# 03_-_Convert.net
KiCad netlist of a schematic drawn in Altium Designer
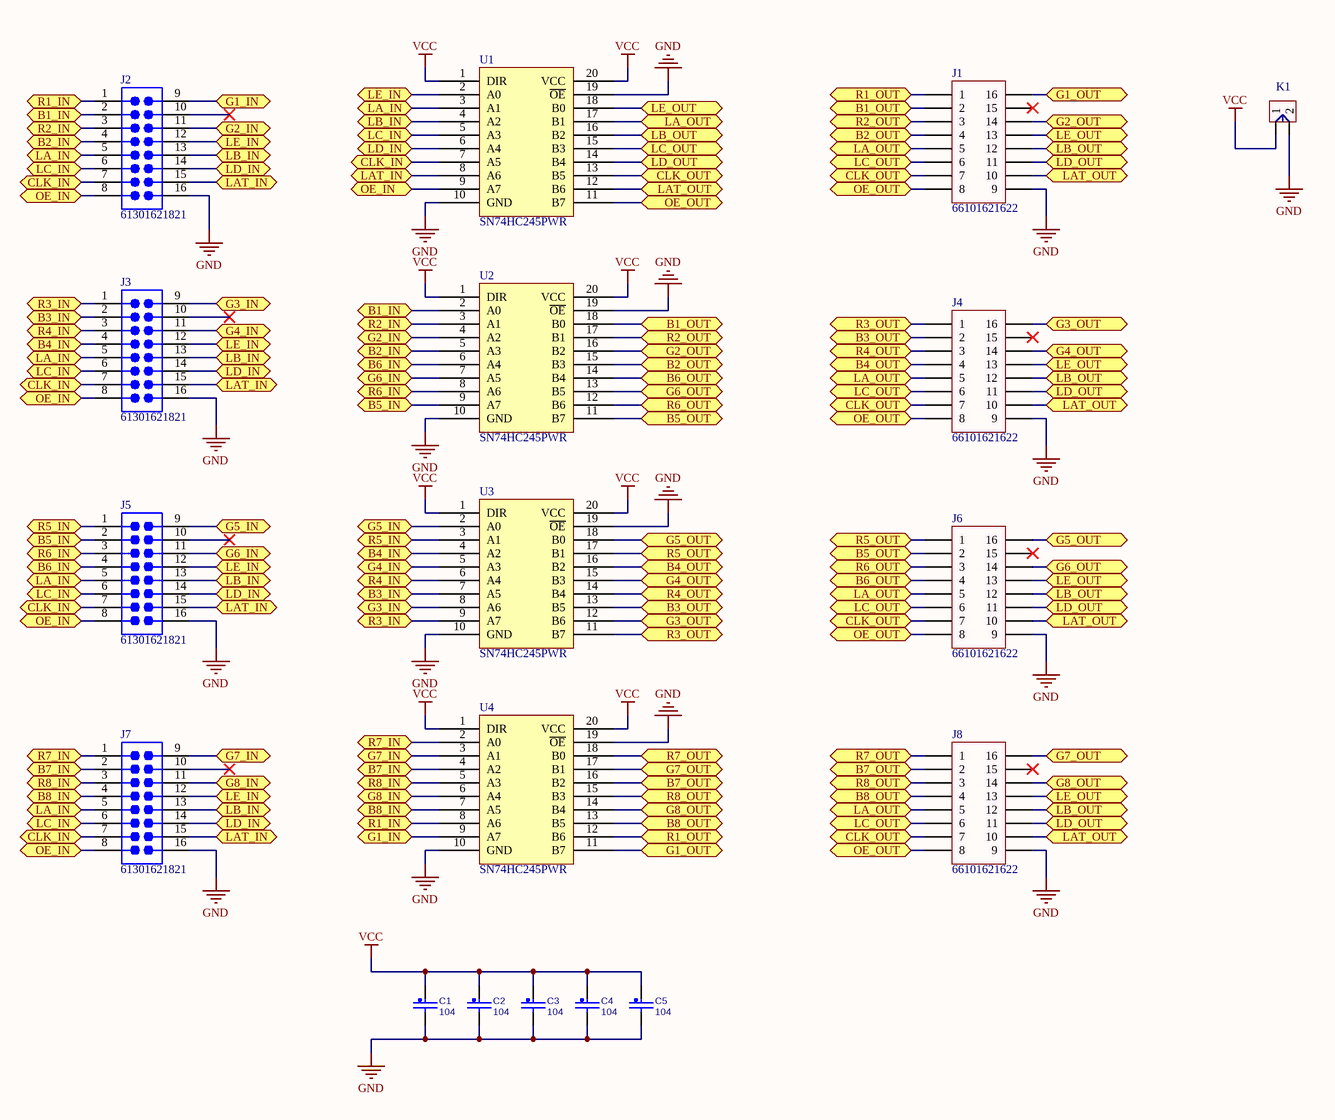
[diagram p0: [03] - Convert.SchDoc]

(export (version "E")
  (design (tool "Eeschema 10.0.6"))
  (components
    (comp (ref "C1")
      (value "104")
      (footprint "C0805")
      (description "Surface Mound Multilayer Ceramic Chip Capacitor (SMD MLCC)")
      (fields
        (field (name "MANUFACTURER") "TDK Corporation")
        (field (name "MANUFACTURER PART NUMBER") "C2012X5R1C226K")
        (field (name ".CHECKED PCB") "RF")
        (field (name ".CHECKED SCH") "RF")
      )
      (libsource (lib "StdLib") (part "CAP-SMD-CERAMIC"))
    )
    (comp (ref "C2")
      (value "104")
      (footprint "C0805")
      (description "Surface Mound Multilayer Ceramic Chip Capacitor (SMD MLCC)")
      (fields
        (field (name "MANUFACTURER") "TDK Corporation")
        (field (name "MANUFACTURER PART NUMBER") "C2012X5R1C226K")
        (field (name ".CHECKED PCB") "RF")
        (field (name ".CHECKED SCH") "RF")
      )
      (libsource (lib "StdLib") (part "CAP-SMD-CERAMIC"))
    )
    (comp (ref "C3")
      (value "104")
      (footprint "C0805")
      (description "Surface Mound Multilayer Ceramic Chip Capacitor (SMD MLCC)")
      (fields
        (field (name "MANUFACTURER") "TDK Corporation")
        (field (name "MANUFACTURER PART NUMBER") "C2012X5R1C226K")
        (field (name ".CHECKED PCB") "RF")
        (field (name ".CHECKED SCH") "RF")
      )
      (libsource (lib "StdLib") (part "CAP-SMD-CERAMIC"))
    )
    (comp (ref "C4")
      (value "104")
      (footprint "C0805")
      (description "Surface Mound Multilayer Ceramic Chip Capacitor (SMD MLCC)")
      (fields
        (field (name "MANUFACTURER") "TDK Corporation")
        (field (name "MANUFACTURER PART NUMBER") "C2012X5R1C226K")
        (field (name ".CHECKED PCB") "RF")
        (field (name ".CHECKED SCH") "RF")
      )
      (libsource (lib "StdLib") (part "CAP-SMD-CERAMIC"))
    )
    (comp (ref "C5")
      (value "104")
      (footprint "C0805")
      (description "Surface Mound Multilayer Ceramic Chip Capacitor (SMD MLCC)")
      (fields
        (field (name "MANUFACTURER") "TDK Corporation")
        (field (name "MANUFACTURER PART NUMBER") "C2012X5R1C226K")
        (field (name ".CHECKED PCB") "RF")
        (field (name ".CHECKED SCH") "RF")
      )
      (libsource (lib "StdLib") (part "CAP-SMD-CERAMIC"))
    )
    (comp (ref "J1")
      (value "66101621622")
      (footprint "66101621622")
      (fields (field (name "MANUFACTURER") "Wurth Elektronik") (field (name "CREATED BY") "Baojun Chen"))
      (libsource (lib "Library") (part "LHeader 16 Dual 2.54MM"))
    )
    (comp (ref "J2")
      (value "61301621821")
      (footprint "61301621821")
      (description "2.54 mm Dual Socket Header, 16p")
      (fields (field (name "PUBLISHER") "Wurth Elektronik"))
      (libsource (lib "Library") (part "JP8 2.54MM Dual Socket"))
    )
    (comp (ref "J3")
      (value "61301621821")
      (footprint "61301621821")
      (description "2.54 mm Dual Socket Header, 16p")
      (fields (field (name "PUBLISHER") "Wurth Elektronik"))
      (libsource (lib "Library") (part "JP8 2.54MM Dual Socket"))
    )
    (comp (ref "J4")
      (value "66101621622")
      (footprint "66101621622")
      (fields (field (name "MANUFACTURER") "Wurth Elektronik") (field (name "CREATED BY") "Baojun Chen"))
      (libsource (lib "Library") (part "LHeader 16 Dual 2.54MM"))
    )
    (comp (ref "J5")
      (value "61301621821")
      (footprint "61301621821")
      (description "2.54 mm Dual Socket Header, 16p")
      (fields (field (name "PUBLISHER") "Wurth Elektronik"))
      (libsource (lib "Library") (part "JP8 2.54MM Dual Socket"))
    )
    (comp (ref "J6")
      (value "66101621622")
      (footprint "66101621622")
      (fields (field (name "MANUFACTURER") "Wurth Elektronik") (field (name "CREATED BY") "Baojun Chen"))
      (libsource (lib "Library") (part "LHeader 16 Dual 2.54MM"))
    )
    (comp (ref "J7")
      (value "61301621821")
      (footprint "61301621821")
      (description "2.54 mm Dual Socket Header, 16p")
      (fields (field (name "PUBLISHER") "Wurth Elektronik"))
      (libsource (lib "Library") (part "JP8 2.54MM Dual Socket"))
    )
    (comp (ref "J8")
      (value "66101621622")
      (footprint "66101621622")
      (fields (field (name "MANUFACTURER") "Wurth Elektronik") (field (name "CREATED BY") "Baojun Chen"))
      (libsource (lib "Library") (part "LHeader 16 Dual 2.54MM"))
    )
    (comp (ref "K1")
      (value "KF2")
      (footprint "KF5.08 2DV")
      (description "KF2, 5.08mm, 10A, 300V, -40C ~ 105C")
      (libsource (lib "Library") (part "KF2"))
    )
    (comp (ref "U1")
      (value "SN74HC245PWR")
      (footprint "TSSOP65P440X650-20N")
      (description "IC Bus Transceiver 8 Bit 20TSSOP / Bus Xcvr Single 8-CH 3-ST 20-PIN TSSOP T/r")
      (fields (field (name "MANUFACTURER") "Texas Instruments"))
      (libsource (lib "StdLib") (part "SN74HC245PWR"))
    )
    (comp (ref "U2")
      (value "SN74HC245PWR")
      (footprint "TSSOP65P440X650-20N")
      (description "IC Bus Transceiver 8 Bit 20TSSOP / Bus Xcvr Single 8-CH 3-ST 20-PIN TSSOP T/r")
      (fields (field (name "MANUFACTURER") "Texas Instruments"))
      (libsource (lib "StdLib") (part "SN74HC245PWR"))
    )
    (comp (ref "U3")
      (value "SN74HC245PWR")
      (footprint "TSSOP65P440X650-20N")
      (description "IC Bus Transceiver 8 Bit 20TSSOP / Bus Xcvr Single 8-CH 3-ST 20-PIN TSSOP T/r")
      (fields (field (name "MANUFACTURER") "Texas Instruments"))
      (libsource (lib "StdLib") (part "SN74HC245PWR"))
    )
    (comp (ref "U4")
      (value "SN74HC245PWR")
      (footprint "TSSOP65P440X650-20N")
      (description "IC Bus Transceiver 8 Bit 20TSSOP / Bus Xcvr Single 8-CH 3-ST 20-PIN TSSOP T/r")
      (fields (field (name "MANUFACTURER") "Texas Instruments"))
      (libsource (lib "StdLib") (part "SN74HC245PWR"))
    )
  )
  (nets
    (net (code "1") (name "/B1_IN") (class "Default")
      (node (ref "J2") (pin "2") (pinfunction "2_2") (pintype "passive"))
      (node (ref "U2") (pin "2") (pinfunction "A0_2") (pintype "passive"))
    )
    (net (code "2") (name "/B1_OUT") (class "Default")
      (node (ref "J1") (pin "2") (pinfunction "2_2") (pintype "passive"))
      (node (ref "U2") (pin "18") (pinfunction "B0_18") (pintype "passive"))
    )
    (net (code "3") (name "/B2_IN") (class "Default")
      (node (ref "J2") (pin "4") (pinfunction "4_4") (pintype "passive"))
      (node (ref "U2") (pin "5") (pinfunction "A3_5") (pintype "passive"))
    )
    (net (code "4") (name "/B2_OUT") (class "Default")
      (node (ref "J1") (pin "4") (pinfunction "4_4") (pintype "passive"))
      (node (ref "U2") (pin "15") (pinfunction "B3_15") (pintype "passive"))
    )
    (net (code "5") (name "/B3_IN") (class "Default")
      (node (ref "J3") (pin "2") (pinfunction "2_2") (pintype "passive"))
      (node (ref "U3") (pin "7") (pinfunction "A5_7") (pintype "passive"))
    )
    (net (code "6") (name "/B3_OUT") (class "Default")
      (node (ref "J4") (pin "2") (pinfunction "2_2") (pintype "passive"))
      (node (ref "U3") (pin "13") (pinfunction "B5_13") (pintype "passive"))
    )
    (net (code "7") (name "/B4_IN") (class "Default")
      (node (ref "J3") (pin "4") (pinfunction "4_4") (pintype "passive"))
      (node (ref "U3") (pin "4") (pinfunction "A2_4") (pintype "passive"))
    )
    (net (code "8") (name "/B4_OUT") (class "Default")
      (node (ref "J4") (pin "4") (pinfunction "4_4") (pintype "passive"))
      (node (ref "U3") (pin "16") (pinfunction "B2_16") (pintype "passive"))
    )
    (net (code "9") (name "/B5_IN") (class "Default")
      (node (ref "J5") (pin "2") (pinfunction "2_2") (pintype "passive"))
      (node (ref "U2") (pin "9") (pinfunction "A7_9") (pintype "passive"))
    )
    (net (code "10") (name "/B5_OUT") (class "Default")
      (node (ref "J6") (pin "2") (pinfunction "2_2") (pintype "passive"))
      (node (ref "U2") (pin "11") (pinfunction "B7_11") (pintype "passive"))
    )
    (net (code "11") (name "/B6_IN") (class "Default")
      (node (ref "J5") (pin "4") (pinfunction "4_4") (pintype "passive"))
      (node (ref "U2") (pin "6") (pinfunction "A4_6") (pintype "passive"))
    )
    (net (code "12") (name "/B6_OUT") (class "Default")
      (node (ref "J6") (pin "4") (pinfunction "4_4") (pintype "passive"))
      (node (ref "U2") (pin "14") (pinfunction "B4_14") (pintype "passive"))
    )
    (net (code "13") (name "/B7_IN") (class "Default")
      (node (ref "J7") (pin "2") (pinfunction "2_2") (pintype "passive"))
      (node (ref "U4") (pin "4") (pinfunction "A2_4") (pintype "passive"))
    )
    (net (code "14") (name "/B7_OUT") (class "Default")
      (node (ref "J8") (pin "2") (pinfunction "2_2") (pintype "passive"))
      (node (ref "U4") (pin "16") (pinfunction "B2_16") (pintype "passive"))
    )
    (net (code "15") (name "/B8_IN") (class "Default")
      (node (ref "J7") (pin "4") (pinfunction "4_4") (pintype "passive"))
      (node (ref "U4") (pin "7") (pinfunction "A5_7") (pintype "passive"))
    )
    (net (code "16") (name "/B8_OUT") (class "Default")
      (node (ref "J8") (pin "4") (pinfunction "4_4") (pintype "passive"))
      (node (ref "U4") (pin "13") (pinfunction "B5_13") (pintype "passive"))
    )
    (net (code "17") (name "/CLK_IN") (class "Default")
      (node (ref "J2") (pin "7") (pinfunction "7_7") (pintype "passive"))
      (node (ref "J3") (pin "7") (pinfunction "7_7") (pintype "passive"))
      (node (ref "J5") (pin "7") (pinfunction "7_7") (pintype "passive"))
      (node (ref "J7") (pin "7") (pinfunction "7_7") (pintype "passive"))
      (node (ref "U1") (pin "7") (pinfunction "A5_7") (pintype "passive"))
    )
    (net (code "18") (name "/CLK_OUT") (class "Default")
      (node (ref "J1") (pin "7") (pinfunction "7_7") (pintype "passive"))
      (node (ref "J4") (pin "7") (pinfunction "7_7") (pintype "passive"))
      (node (ref "J6") (pin "7") (pinfunction "7_7") (pintype "passive"))
      (node (ref "J8") (pin "7") (pinfunction "7_7") (pintype "passive"))
      (node (ref "U1") (pin "13") (pinfunction "B5_13") (pintype "passive"))
    )
    (net (code "19") (name "/G1_IN") (class "Default")
      (node (ref "J2") (pin "9") (pinfunction "9_9") (pintype "passive"))
      (node (ref "U4") (pin "9") (pinfunction "A7_9") (pintype "passive"))
    )
    (net (code "20") (name "/G1_OUT") (class "Default")
      (node (ref "J1") (pin "16") (pinfunction "16_16") (pintype "passive"))
      (node (ref "U4") (pin "11") (pinfunction "B7_11") (pintype "passive"))
    )
    (net (code "21") (name "/G2_IN") (class "Default")
      (node (ref "J2") (pin "11") (pinfunction "11_11") (pintype "passive"))
      (node (ref "U2") (pin "4") (pinfunction "A2_4") (pintype "passive"))
    )
    (net (code "22") (name "/G2_OUT") (class "Default")
      (node (ref "J1") (pin "14") (pinfunction "14_14") (pintype "passive"))
      (node (ref "U2") (pin "16") (pinfunction "B2_16") (pintype "passive"))
    )
    (net (code "23") (name "/G3_IN") (class "Default")
      (node (ref "J3") (pin "9") (pinfunction "9_9") (pintype "passive"))
      (node (ref "U3") (pin "8") (pinfunction "A6_8") (pintype "passive"))
    )
    (net (code "24") (name "/G3_OUT") (class "Default")
      (node (ref "J4") (pin "16") (pinfunction "16_16") (pintype "passive"))
      (node (ref "U3") (pin "12") (pinfunction "B6_12") (pintype "passive"))
    )
    (net (code "25") (name "/G4_IN") (class "Default")
      (node (ref "J3") (pin "11") (pinfunction "11_11") (pintype "passive"))
      (node (ref "U3") (pin "5") (pinfunction "A3_5") (pintype "passive"))
    )
    (net (code "26") (name "/G4_OUT") (class "Default")
      (node (ref "J4") (pin "14") (pinfunction "14_14") (pintype "passive"))
      (node (ref "U3") (pin "15") (pinfunction "B3_15") (pintype "passive"))
    )
    (net (code "27") (name "/G5_IN") (class "Default")
      (node (ref "J5") (pin "9") (pinfunction "9_9") (pintype "passive"))
      (node (ref "U3") (pin "2") (pinfunction "A0_2") (pintype "passive"))
    )
    (net (code "28") (name "/G5_OUT") (class "Default")
      (node (ref "J6") (pin "16") (pinfunction "16_16") (pintype "passive"))
      (node (ref "U3") (pin "18") (pinfunction "B0_18") (pintype "passive"))
    )
    (net (code "29") (name "/G6_IN") (class "Default")
      (node (ref "J5") (pin "11") (pinfunction "11_11") (pintype "passive"))
      (node (ref "U2") (pin "7") (pinfunction "A5_7") (pintype "passive"))
    )
    (net (code "30") (name "/G6_OUT") (class "Default")
      (node (ref "J6") (pin "14") (pinfunction "14_14") (pintype "passive"))
      (node (ref "U2") (pin "13") (pinfunction "B5_13") (pintype "passive"))
    )
    (net (code "31") (name "/G7_IN") (class "Default")
      (node (ref "J7") (pin "9") (pinfunction "9_9") (pintype "passive"))
      (node (ref "U4") (pin "3") (pinfunction "A1_3") (pintype "passive"))
    )
    (net (code "32") (name "/G7_OUT") (class "Default")
      (node (ref "J8") (pin "16") (pinfunction "16_16") (pintype "passive"))
      (node (ref "U4") (pin "17") (pinfunction "B1_17") (pintype "passive"))
    )
    (net (code "33") (name "/G8_IN") (class "Default")
      (node (ref "J7") (pin "11") (pinfunction "11_11") (pintype "passive"))
      (node (ref "U4") (pin "6") (pinfunction "A4_6") (pintype "passive"))
    )
    (net (code "34") (name "/G8_OUT") (class "Default")
      (node (ref "J8") (pin "14") (pinfunction "14_14") (pintype "passive"))
      (node (ref "U4") (pin "14") (pinfunction "B4_14") (pintype "passive"))
    )
    (net (code "35") (name "/LAT_IN") (class "Default")
      (node (ref "J2") (pin "15") (pinfunction "15_15") (pintype "passive"))
      (node (ref "J3") (pin "15") (pinfunction "15_15") (pintype "passive"))
      (node (ref "J5") (pin "15") (pinfunction "15_15") (pintype "passive"))
      (node (ref "J7") (pin "15") (pinfunction "15_15") (pintype "passive"))
      (node (ref "U1") (pin "8") (pinfunction "A6_8") (pintype "passive"))
    )
    (net (code "36") (name "/LAT_OUT") (class "Default")
      (node (ref "J1") (pin "10") (pinfunction "10_10") (pintype "passive"))
      (node (ref "J4") (pin "10") (pinfunction "10_10") (pintype "passive"))
      (node (ref "J6") (pin "10") (pinfunction "10_10") (pintype "passive"))
      (node (ref "J8") (pin "10") (pinfunction "10_10") (pintype "passive"))
      (node (ref "U1") (pin "12") (pinfunction "B6_12") (pintype "passive"))
    )
    (net (code "37") (name "/LA_IN") (class "Default")
      (node (ref "J2") (pin "5") (pinfunction "5_5") (pintype "passive"))
      (node (ref "J3") (pin "5") (pinfunction "5_5") (pintype "passive"))
      (node (ref "J5") (pin "5") (pinfunction "5_5") (pintype "passive"))
      (node (ref "J7") (pin "5") (pinfunction "5_5") (pintype "passive"))
      (node (ref "U1") (pin "3") (pinfunction "A1_3") (pintype "passive"))
    )
    (net (code "38") (name "/LA_OUT") (class "Default")
      (node (ref "J1") (pin "5") (pinfunction "5_5") (pintype "passive"))
      (node (ref "J4") (pin "5") (pinfunction "5_5") (pintype "passive"))
      (node (ref "J6") (pin "5") (pinfunction "5_5") (pintype "passive"))
      (node (ref "J8") (pin "5") (pinfunction "5_5") (pintype "passive"))
      (node (ref "U1") (pin "17") (pinfunction "B1_17") (pintype "passive"))
    )
    (net (code "39") (name "/LB_IN") (class "Default")
      (node (ref "J2") (pin "13") (pinfunction "13_13") (pintype "passive"))
      (node (ref "J3") (pin "13") (pinfunction "13_13") (pintype "passive"))
      (node (ref "J5") (pin "13") (pinfunction "13_13") (pintype "passive"))
      (node (ref "J7") (pin "13") (pinfunction "13_13") (pintype "passive"))
      (node (ref "U1") (pin "4") (pinfunction "A2_4") (pintype "passive"))
    )
    (net (code "40") (name "/LB_OUT") (class "Default")
      (node (ref "J1") (pin "12") (pinfunction "12_12") (pintype "passive"))
      (node (ref "J4") (pin "12") (pinfunction "12_12") (pintype "passive"))
      (node (ref "J6") (pin "12") (pinfunction "12_12") (pintype "passive"))
      (node (ref "J8") (pin "12") (pinfunction "12_12") (pintype "passive"))
      (node (ref "U1") (pin "16") (pinfunction "B2_16") (pintype "passive"))
    )
    (net (code "41") (name "/LC_IN") (class "Default")
      (node (ref "J2") (pin "6") (pinfunction "6_6") (pintype "passive"))
      (node (ref "J3") (pin "6") (pinfunction "6_6") (pintype "passive"))
      (node (ref "J5") (pin "6") (pinfunction "6_6") (pintype "passive"))
      (node (ref "J7") (pin "6") (pinfunction "6_6") (pintype "passive"))
      (node (ref "U1") (pin "5") (pinfunction "A3_5") (pintype "passive"))
    )
    (net (code "42") (name "/LC_OUT") (class "Default")
      (node (ref "J1") (pin "6") (pinfunction "6_6") (pintype "passive"))
      (node (ref "J4") (pin "6") (pinfunction "6_6") (pintype "passive"))
      (node (ref "J6") (pin "6") (pinfunction "6_6") (pintype "passive"))
      (node (ref "J8") (pin "6") (pinfunction "6_6") (pintype "passive"))
      (node (ref "U1") (pin "15") (pinfunction "B3_15") (pintype "passive"))
    )
    (net (code "43") (name "/LD_IN") (class "Default")
      (node (ref "J2") (pin "14") (pinfunction "14_14") (pintype "passive"))
      (node (ref "J3") (pin "14") (pinfunction "14_14") (pintype "passive"))
      (node (ref "J5") (pin "14") (pinfunction "14_14") (pintype "passive"))
      (node (ref "J7") (pin "14") (pinfunction "14_14") (pintype "passive"))
      (node (ref "U1") (pin "6") (pinfunction "A4_6") (pintype "passive"))
    )
    (net (code "44") (name "/LD_OUT") (class "Default")
      (node (ref "J1") (pin "11") (pinfunction "11_11") (pintype "passive"))
      (node (ref "J4") (pin "11") (pinfunction "11_11") (pintype "passive"))
      (node (ref "J6") (pin "11") (pinfunction "11_11") (pintype "passive"))
      (node (ref "J8") (pin "11") (pinfunction "11_11") (pintype "passive"))
      (node (ref "U1") (pin "14") (pinfunction "B4_14") (pintype "passive"))
    )
    (net (code "45") (name "/LE_IN") (class "Default")
      (node (ref "J2") (pin "12") (pinfunction "12_12") (pintype "passive"))
      (node (ref "J3") (pin "12") (pinfunction "12_12") (pintype "passive"))
      (node (ref "J5") (pin "12") (pinfunction "12_12") (pintype "passive"))
      (node (ref "J7") (pin "12") (pinfunction "12_12") (pintype "passive"))
      (node (ref "U1") (pin "2") (pinfunction "A0_2") (pintype "passive"))
    )
    (net (code "46") (name "/LE_OUT") (class "Default")
      (node (ref "J1") (pin "13") (pinfunction "13_13") (pintype "passive"))
      (node (ref "J4") (pin "13") (pinfunction "13_13") (pintype "passive"))
      (node (ref "J6") (pin "13") (pinfunction "13_13") (pintype "passive"))
      (node (ref "J8") (pin "13") (pinfunction "13_13") (pintype "passive"))
      (node (ref "U1") (pin "18") (pinfunction "B0_18") (pintype "passive"))
    )
    (net (code "47") (name "/OE_IN") (class "Default")
      (node (ref "J2") (pin "8") (pinfunction "8_8") (pintype "passive"))
      (node (ref "J3") (pin "8") (pinfunction "8_8") (pintype "passive"))
      (node (ref "J5") (pin "8") (pinfunction "8_8") (pintype "passive"))
      (node (ref "J7") (pin "8") (pinfunction "8_8") (pintype "passive"))
      (node (ref "U1") (pin "9") (pinfunction "A7_9") (pintype "passive"))
    )
    (net (code "48") (name "/OE_OUT") (class "Default")
      (node (ref "J1") (pin "8") (pinfunction "8_8") (pintype "passive"))
      (node (ref "J4") (pin "8") (pinfunction "8_8") (pintype "passive"))
      (node (ref "J6") (pin "8") (pinfunction "8_8") (pintype "passive"))
      (node (ref "J8") (pin "8") (pinfunction "8_8") (pintype "passive"))
      (node (ref "U1") (pin "11") (pinfunction "B7_11") (pintype "passive"))
    )
    (net (code "49") (name "/R1_IN") (class "Default")
      (node (ref "J2") (pin "1") (pinfunction "1_1") (pintype "passive"))
      (node (ref "U4") (pin "8") (pinfunction "A6_8") (pintype "passive"))
    )
    (net (code "50") (name "/R1_OUT") (class "Default")
      (node (ref "J1") (pin "1") (pinfunction "1_1") (pintype "passive"))
      (node (ref "U4") (pin "12") (pinfunction "B6_12") (pintype "passive"))
    )
    (net (code "51") (name "/R2_IN") (class "Default")
      (node (ref "J2") (pin "3") (pinfunction "3_3") (pintype "passive"))
      (node (ref "U2") (pin "3") (pinfunction "A1_3") (pintype "passive"))
    )
    (net (code "52") (name "/R2_OUT") (class "Default")
      (node (ref "J1") (pin "3") (pinfunction "3_3") (pintype "passive"))
      (node (ref "U2") (pin "17") (pinfunction "B1_17") (pintype "passive"))
    )
    (net (code "53") (name "/R3_IN") (class "Default")
      (node (ref "J3") (pin "1") (pinfunction "1_1") (pintype "passive"))
      (node (ref "U3") (pin "9") (pinfunction "A7_9") (pintype "passive"))
    )
    (net (code "54") (name "/R3_OUT") (class "Default")
      (node (ref "J4") (pin "1") (pinfunction "1_1") (pintype "passive"))
      (node (ref "U3") (pin "11") (pinfunction "B7_11") (pintype "passive"))
    )
    (net (code "55") (name "/R4_IN") (class "Default")
      (node (ref "J3") (pin "3") (pinfunction "3_3") (pintype "passive"))
      (node (ref "U3") (pin "6") (pinfunction "A4_6") (pintype "passive"))
    )
    (net (code "56") (name "/R4_OUT") (class "Default")
      (node (ref "J4") (pin "3") (pinfunction "3_3") (pintype "passive"))
      (node (ref "U3") (pin "14") (pinfunction "B4_14") (pintype "passive"))
    )
    (net (code "57") (name "/R5_IN") (class "Default")
      (node (ref "J5") (pin "1") (pinfunction "1_1") (pintype "passive"))
      (node (ref "U3") (pin "3") (pinfunction "A1_3") (pintype "passive"))
    )
    (net (code "58") (name "/R5_OUT") (class "Default")
      (node (ref "J6") (pin "1") (pinfunction "1_1") (pintype "passive"))
      (node (ref "U3") (pin "17") (pinfunction "B1_17") (pintype "passive"))
    )
    (net (code "59") (name "/R6_IN") (class "Default")
      (node (ref "J5") (pin "3") (pinfunction "3_3") (pintype "passive"))
      (node (ref "U2") (pin "8") (pinfunction "A6_8") (pintype "passive"))
    )
    (net (code "60") (name "/R6_OUT") (class "Default")
      (node (ref "J6") (pin "3") (pinfunction "3_3") (pintype "passive"))
      (node (ref "U2") (pin "12") (pinfunction "B6_12") (pintype "passive"))
    )
    (net (code "61") (name "/R7_IN") (class "Default")
      (node (ref "J7") (pin "1") (pinfunction "1_1") (pintype "passive"))
      (node (ref "U4") (pin "2") (pinfunction "A0_2") (pintype "passive"))
    )
    (net (code "62") (name "/R7_OUT") (class "Default")
      (node (ref "J8") (pin "1") (pinfunction "1_1") (pintype "passive"))
      (node (ref "U4") (pin "18") (pinfunction "B0_18") (pintype "passive"))
    )
    (net (code "63") (name "/R8_IN") (class "Default")
      (node (ref "J7") (pin "3") (pinfunction "3_3") (pintype "passive"))
      (node (ref "U4") (pin "5") (pinfunction "A3_5") (pintype "passive"))
    )
    (net (code "64") (name "/R8_OUT") (class "Default")
      (node (ref "J8") (pin "3") (pinfunction "3_3") (pintype "passive"))
      (node (ref "U4") (pin "15") (pinfunction "B3_15") (pintype "passive"))
    )
    (net (code "65") (name "GND") (class "Default")
      (node (ref "C1") (pin "2") (pinfunction "2_2") (pintype "passive"))
      (node (ref "C2") (pin "2") (pinfunction "2_2") (pintype "passive"))
      (node (ref "C3") (pin "2") (pinfunction "2_2") (pintype "passive"))
      (node (ref "C4") (pin "2") (pinfunction "2_2") (pintype "passive"))
      (node (ref "C5") (pin "2") (pinfunction "2_2") (pintype "passive"))
      (node (ref "J1") (pin "9") (pinfunction "9_9") (pintype "passive"))
      (node (ref "J2") (pin "16") (pinfunction "16_16") (pintype "passive"))
      (node (ref "J3") (pin "16") (pinfunction "16_16") (pintype "passive"))
      (node (ref "J4") (pin "9") (pinfunction "9_9") (pintype "passive"))
      (node (ref "J5") (pin "16") (pinfunction "16_16") (pintype "passive"))
      (node (ref "J6") (pin "9") (pinfunction "9_9") (pintype "passive"))
      (node (ref "J7") (pin "16") (pinfunction "16_16") (pintype "passive"))
      (node (ref "J8") (pin "9") (pinfunction "9_9") (pintype "passive"))
      (node (ref "K1") (pin "2") (pinfunction "2_2") (pintype "passive"))
      (node (ref "U1") (pin "10") (pinfunction "GND_10") (pintype "passive"))
      (node (ref "U1") (pin "19") (pinfunction "~{OE}_19") (pintype "passive"))
      (node (ref "U2") (pin "10") (pinfunction "GND_10") (pintype "passive"))
      (node (ref "U2") (pin "19") (pinfunction "~{OE}_19") (pintype "passive"))
      (node (ref "U3") (pin "10") (pinfunction "GND_10") (pintype "passive"))
      (node (ref "U3") (pin "19") (pinfunction "~{OE}_19") (pintype "passive"))
      (node (ref "U4") (pin "10") (pinfunction "GND_10") (pintype "passive"))
      (node (ref "U4") (pin "19") (pinfunction "~{OE}_19") (pintype "passive"))
    )
    (net (code "66") (name "VCC") (class "Default")
      (node (ref "C1") (pin "1") (pinfunction "1_1") (pintype "passive"))
      (node (ref "C2") (pin "1") (pinfunction "1_1") (pintype "passive"))
      (node (ref "C3") (pin "1") (pinfunction "1_1") (pintype "passive"))
      (node (ref "C4") (pin "1") (pinfunction "1_1") (pintype "passive"))
      (node (ref "C5") (pin "1") (pinfunction "1_1") (pintype "passive"))
      (node (ref "K1") (pin "1") (pinfunction "1_1") (pintype "passive"))
      (node (ref "U1") (pin "1") (pinfunction "DIR_1") (pintype "passive"))
      (node (ref "U1") (pin "20") (pinfunction "VCC_20") (pintype "passive"))
      (node (ref "U2") (pin "1") (pinfunction "DIR_1") (pintype "passive"))
      (node (ref "U2") (pin "20") (pinfunction "VCC_20") (pintype "passive"))
      (node (ref "U3") (pin "1") (pinfunction "DIR_1") (pintype "passive"))
      (node (ref "U3") (pin "20") (pinfunction "VCC_20") (pintype "passive"))
      (node (ref "U4") (pin "1") (pinfunction "DIR_1") (pintype "passive"))
      (node (ref "U4") (pin "20") (pinfunction "VCC_20") (pintype "passive"))
    )
    (net (code "67") (name "unconnected-(J1-Pad15)") (class "Default")
      (node (ref "J1") (pin "15") (pinfunction "15_15") (pintype "passive+no_connect"))
    )
    (net (code "68") (name "unconnected-(J2-Pad10)") (class "Default")
      (node (ref "J2") (pin "10") (pinfunction "10_10") (pintype "passive+no_connect"))
    )
    (net (code "69") (name "unconnected-(J3-Pad10)") (class "Default")
      (node (ref "J3") (pin "10") (pinfunction "10_10") (pintype "passive+no_connect"))
    )
    (net (code "70") (name "unconnected-(J4-Pad15)") (class "Default")
      (node (ref "J4") (pin "15") (pinfunction "15_15") (pintype "passive+no_connect"))
    )
    (net (code "71") (name "unconnected-(J5-Pad10)") (class "Default")
      (node (ref "J5") (pin "10") (pinfunction "10_10") (pintype "passive+no_connect"))
    )
    (net (code "72") (name "unconnected-(J6-Pad15)") (class "Default")
      (node (ref "J6") (pin "15") (pinfunction "15_15") (pintype "passive+no_connect"))
    )
    (net (code "73") (name "unconnected-(J7-Pad10)") (class "Default")
      (node (ref "J7") (pin "10") (pinfunction "10_10") (pintype "passive+no_connect"))
    )
    (net (code "74") (name "unconnected-(J8-Pad15)") (class "Default")
      (node (ref "J8") (pin "15") (pinfunction "15_15") (pintype "passive+no_connect"))
    )
  )
)
